# Charging_sch.net
KiCad netlist of a schematic drawn in Altium Designer
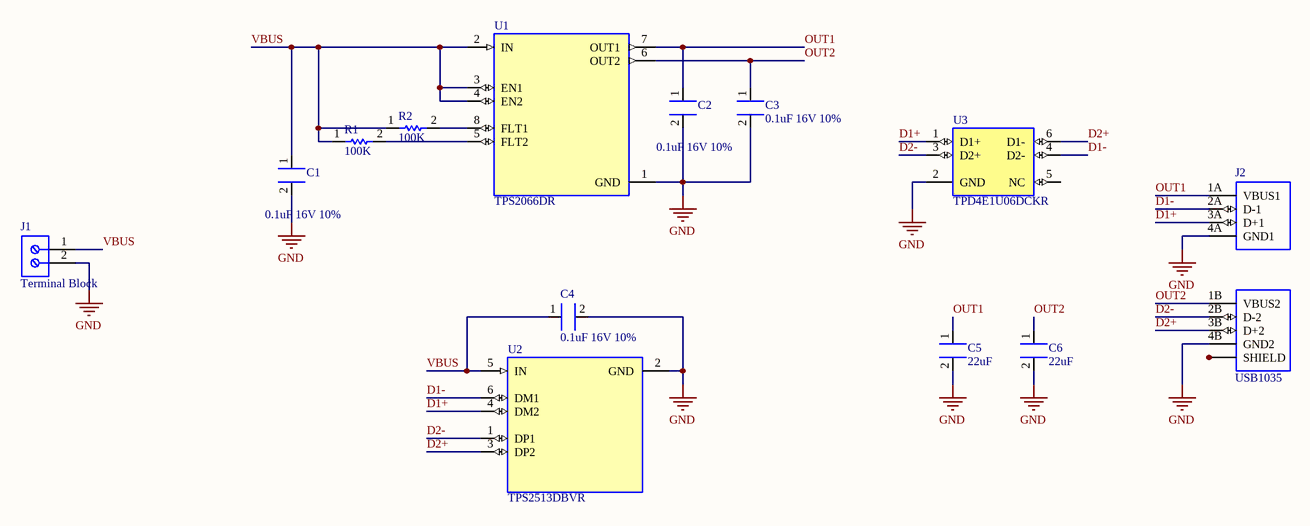
[diagram p0: Charging_sch.SchDoc]

(export (version "E")
  (design (tool "Eeschema 10.0.6"))
  (components
    (comp (ref "C1")
      (value "0.1uF 16V 10%")
      (footprint "C0805C104K8RAC7800")
      (description "贴片电容（MLCC） 100nF ±10% 50V X7R 0805")
      (fields
        (field (name "MANUFACTURER") "Yageo")
        (field (name "MANUFACTURER PART NUMBER") "CC0805KRX7R9BB104")
      )
      (libsource (lib "Schlib2") (part "CC0805KRX7R9BB104"))
    )
    (comp (ref "C2")
      (value "0.1uF 16V 10%")
      (footprint "C0805C104K8RAC7800")
      (description "贴片电容（MLCC） 100nF ±10% 50V X7R 0805")
      (fields
        (field (name "MANUFACTURER") "Yageo")
        (field (name "MANUFACTURER PART NUMBER") "CC0805KRX7R9BB104")
      )
      (libsource (lib "Schlib2") (part "CC0805KRX7R9BB104"))
    )
    (comp (ref "C3")
      (value "0.1uF 16V 10%")
      (footprint "C0805C104K8RAC7800")
      (description "贴片电容（MLCC） 100nF ±10% 50V X7R 0805")
      (fields
        (field (name "MANUFACTURER") "Yageo")
        (field (name "MANUFACTURER PART NUMBER") "CC0805KRX7R9BB104")
      )
      (libsource (lib "Schlib2") (part "CC0805KRX7R9BB104"))
    )
    (comp (ref "C4")
      (value "0.1uF 16V 10%")
      (footprint "C0805C104K8RAC7800")
      (description "贴片电容（MLCC） 100nF ±10% 50V X7R 0805")
      (fields
        (field (name "MANUFACTURER") "Yageo")
        (field (name "MANUFACTURER PART NUMBER") "CC0805KRX7R9BB104")
      )
      (libsource (lib "Schlib2") (part "CC0805KRX7R9BB104"))
    )
    (comp (ref "C5")
      (value "22uF")
      (footprint "RVT1C220M0405")
      (fields
        (field (name "MANUFACTURER") "ROQANG")
        (field (name "MANUFACTURER PART NUMBER") "RVT1C220M0405")
      )
      (libsource (lib "Schlib2") (part "RVT1C220M0405"))
    )
    (comp (ref "C6")
      (value "22uF")
      (footprint "RVT1C220M0405")
      (fields
        (field (name "MANUFACTURER") "ROQANG")
        (field (name "MANUFACTURER PART NUMBER") "RVT1C220M0405")
      )
      (libsource (lib "Schlib2") (part "RVT1C220M0405"))
    )
    (comp (ref "J1")
      (value "Terminal Block")
      (footprint "Terminal Block")
      (description "Conn Terminal Block F 2 POS 5mm Solder RA SMD 6A T/R")
      (fields
        (field (name "MANUFACTURER") "Wurth Electronics Midcom")
        (field (name "MANUFACTURER PART NUMBER") "691709710302")
      )
      (libsource (lib "Schlib1") (part "691709710302"))
    )
    (comp (ref "J2")
      (value "USB1035")
      (footprint "USB1035")
      (description "USB1035 Series 8 Position Dual Port Through Hole USB")
      (fields
        (field (name "MANUFACTURER") "Global Connector Technology")
        (field (name "MANUFACTURER PART NUMBER") "USB1035-GF-P-0-B-B")
      )
      (libsource (lib "Schlib1") (part "USB1035-GF-P-0-B-B"))
    )
    (comp (ref "R1")
      (value "100K")
      (footprint "ARG05FTC1003")
      (fields
        (field (name "MANUFACTURER") "Viking Tech")
        (field (name "MANUFACTURER PART NUMBER") "ARG05FTC1003")
      )
      (libsource (lib "Schlib2") (part "ARG05FTC1003"))
    )
    (comp (ref "R2")
      (value "100K")
      (footprint "ARG05FTC1003")
      (fields
        (field (name "MANUFACTURER") "Viking Tech")
        (field (name "MANUFACTURER PART NUMBER") "ARG05FTC1003")
      )
      (libsource (lib "Schlib2") (part "ARG05FTC1003"))
    )
    (comp (ref "U1")
      (value "TPS2066DR")
      (footprint "TPS2066DR")
      (description "Dual 1A, active-high, current-limited, power-distribution switches 8-SOIC -40 to 85")
      (fields (field (name "MANUFACTURER") "Texas Instruments"))
      (libsource (lib "Schlib2") (part "TPS2066DR"))
    )
    (comp (ref "U2")
      (value "TPS2513DBVR")
      (footprint "TPS2513DBVR")
      (description "USB Charging Port Controller Dual 5.5V 6-Pin SOT-23 T/R / IC USB PWR SW/CTRLR CHRG SOT23-6")
      (fields (field (name "MANUFACTURER") "Texas Instruments"))
      (libsource (lib "Schlib2") (part "TPS2513DBVR"))
    )
    (comp (ref "U3")
      (value "TPD4E1U06DCKR")
      (footprint "TPD4E1U06DCKR")
      (description "TVS DIODE 5.5VWM 15VC SC70-6")
      (fields (field (name "MANUFACTURER") "Texas Instruments"))
      (libsource (lib "Schlib2") (part "TPD4E1U06DCKR"))
    )
  )
  (nets
    (net (code "1") (name "/D1+") (class "Default")
      (node (ref "J2") (pin "3A") (pinfunction "D+1_3A") (pintype "bidirectional"))
      (node (ref "U2") (pin "4") (pinfunction "DM2_4") (pintype "bidirectional"))
      (node (ref "U3") (pin "1") (pinfunction "D1+_1") (pintype "bidirectional"))
    )
    (net (code "2") (name "/D1-") (class "Default")
      (node (ref "J2") (pin "2A") (pinfunction "D-1_2A") (pintype "bidirectional"))
      (node (ref "U2") (pin "6") (pinfunction "DM1_6") (pintype "bidirectional"))
      (node (ref "U3") (pin "4") (pinfunction "D2-_4") (pintype "bidirectional"))
    )
    (net (code "3") (name "/D2+") (class "Default")
      (node (ref "J2") (pin "3B") (pinfunction "D+2_3B") (pintype "bidirectional"))
      (node (ref "U2") (pin "3") (pinfunction "DP2_3") (pintype "bidirectional"))
      (node (ref "U3") (pin "6") (pinfunction "D1-_6") (pintype "bidirectional"))
    )
    (net (code "4") (name "/D2-") (class "Default")
      (node (ref "J2") (pin "2B") (pinfunction "D-2_2B") (pintype "bidirectional"))
      (node (ref "U2") (pin "1") (pinfunction "DP1_1") (pintype "bidirectional"))
      (node (ref "U3") (pin "3") (pinfunction "D2+_3") (pintype "bidirectional"))
    )
    (net (code "5") (name "/OUT1") (class "Default")
      (node (ref "C2") (pin "1") (pinfunction "1_1") (pintype "passive"))
      (node (ref "C5") (pin "1") (pinfunction "1_1") (pintype "passive"))
      (node (ref "J2") (pin "1A") (pinfunction "VBUS1_1A") (pintype "power_in"))
      (node (ref "U1") (pin "7") (pinfunction "OUT1_7") (pintype "output"))
    )
    (net (code "6") (name "/OUT2") (class "Default")
      (node (ref "C3") (pin "1") (pinfunction "1_1") (pintype "passive"))
      (node (ref "C6") (pin "1") (pinfunction "1_1") (pintype "passive"))
      (node (ref "J2") (pin "1B") (pinfunction "VBUS2_1B") (pintype "power_in"))
      (node (ref "U1") (pin "6") (pinfunction "OUT2_6") (pintype "output"))
    )
    (net (code "7") (name "/VBUS") (class "Default")
      (node (ref "C1") (pin "1") (pinfunction "1_1") (pintype "passive"))
      (node (ref "C4") (pin "1") (pinfunction "1_1") (pintype "passive"))
      (node (ref "J1") (pin "1") (pinfunction "1_1") (pintype "passive"))
      (node (ref "R1") (pin "1") (pinfunction "1_1") (pintype "passive"))
      (node (ref "R2") (pin "1") (pinfunction "1_1") (pintype "passive"))
      (node (ref "U1") (pin "2") (pinfunction "IN_2") (pintype "input"))
      (node (ref "U1") (pin "3") (pinfunction "EN1_3") (pintype "bidirectional"))
      (node (ref "U1") (pin "4") (pinfunction "EN2_4") (pintype "bidirectional"))
      (node (ref "U2") (pin "5") (pinfunction "IN_5") (pintype "input"))
    )
    (net (code "8") (name "GND") (class "Default")
      (node (ref "C1") (pin "2") (pinfunction "2_2") (pintype "passive"))
      (node (ref "C2") (pin "2") (pinfunction "2_2") (pintype "passive"))
      (node (ref "C3") (pin "2") (pinfunction "2_2") (pintype "passive"))
      (node (ref "C4") (pin "2") (pinfunction "2_2") (pintype "passive"))
      (node (ref "C5") (pin "2") (pinfunction "2_2") (pintype "passive"))
      (node (ref "C6") (pin "2") (pinfunction "2_2") (pintype "passive"))
      (node (ref "J1") (pin "2") (pinfunction "2_2") (pintype "passive"))
      (node (ref "J2") (pin "4A") (pinfunction "GND1_4A") (pintype "power_in"))
      (node (ref "J2") (pin "4B") (pinfunction "GND2_4B") (pintype "power_in"))
      (node (ref "U1") (pin "1") (pinfunction "GND_1") (pintype "power_in"))
      (node (ref "U2") (pin "2") (pinfunction "GND_2") (pintype "power_in"))
      (node (ref "U3") (pin "2") (pinfunction "GND_2") (pintype "power_in"))
    )
    (net (code "9") (name "Net-(J2-SHIELD-Pad10)") (class "Default")
      (node (ref "J2") (pin "10") (pinfunction "SHIELD_10") (pintype "power_in"))
      (node (ref "J2") (pin "11") (pinfunction "SHIELD_11") (pintype "power_in"))
      (node (ref "J2") (pin "12") (pinfunction "SHIELD_12") (pintype "power_in"))
      (node (ref "J2") (pin "9") (pinfunction "SHIELD_9") (pintype "power_in"))
    )
    (net (code "10") (name "Net-(U1-FLT1)") (class "Default")
      (node (ref "R2") (pin "2") (pinfunction "2_2") (pintype "passive"))
      (node (ref "U1") (pin "8") (pinfunction "FLT1_8") (pintype "bidirectional"))
    )
    (net (code "11") (name "Net-(U1-FLT2)") (class "Default")
      (node (ref "R1") (pin "2") (pinfunction "2_2") (pintype "passive"))
      (node (ref "U1") (pin "5") (pinfunction "FLT2_5") (pintype "bidirectional"))
    )
    (net (code "12") (name "unconnected-(U3-NC-Pad5)") (class "Default")
      (node (ref "U3") (pin "5") (pinfunction "NC_5") (pintype "bidirectional"))
    )
  )
)
